# RGB_LED.net
KiCad netlist of a schematic drawn in Altium Designer
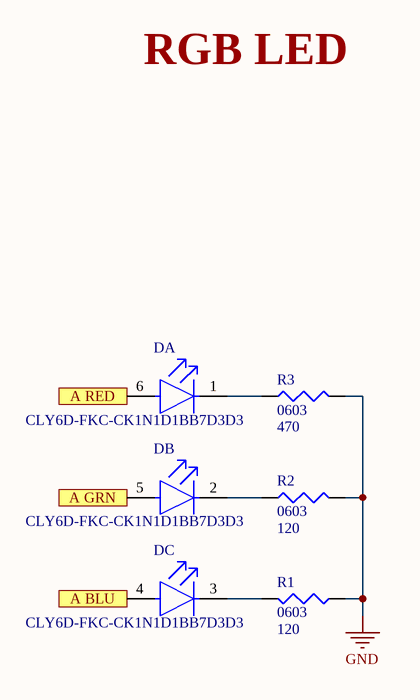
[diagram p0: RGB LED.SchDoc]

(export (version "E")
  (design (tool "Eeschema 10.0.6"))
  (components
    (comp (ref "D")
      (value "CLY6D-FKC-CK1N1D1BB7D3D3")
      (footprint "FP-CLY6D-FKC-MFG")
      (description "LED RGB DIFFUSED 6PLCC SMD")
      (libsource (lib "Altium Content Vault") (part "675964bc96c2f6a68928e7004de3fc3"))
    )
    (comp (ref "R1")
      (value "0603")
      (footprint "J1-0603")
      (description "Resistor")
      (fields (field (name "ALTIUM_VALUE") "120") (field (name "PUBLISHER") "Altium Limited"))
      (libsource (lib "Miscellaneous Devices") (part "Res3"))
    )
    (comp (ref "R2")
      (value "0603")
      (footprint "J1-0603")
      (description "Resistor")
      (fields (field (name "ALTIUM_VALUE") "120") (field (name "PUBLISHER") "Altium Limited"))
      (libsource (lib "Miscellaneous Devices") (part "Res3"))
    )
    (comp (ref "R3")
      (value "0603")
      (footprint "J1-0603")
      (description "Resistor")
      (fields (field (name "ALTIUM_VALUE") "470") (field (name "PUBLISHER") "Altium Limited"))
      (libsource (lib "Miscellaneous Devices") (part "Res3"))
    )
  )
  (nets
    (net (code "1") (name "/A BLU") (class "Default")
      (node (ref "D") (pin "4") (pinfunction "RED(A)_4") (pintype "passive"))
    )
    (net (code "2") (name "/A GRN") (class "Default")
      (node (ref "D") (pin "5") (pinfunction "GREEN(A)_5") (pintype "passive"))
    )
    (net (code "3") (name "/A RED") (class "Default")
      (node (ref "D") (pin "6") (pinfunction "BLUE(A)_6") (pintype "passive"))
    )
    (net (code "4") (name "GND") (class "Default")
      (node (ref "R1") (pin "1") (pinfunction "1_1") (pintype "passive"))
      (node (ref "R2") (pin "2") (pinfunction "2_2") (pintype "passive"))
      (node (ref "R3") (pin "2") (pinfunction "2_2") (pintype "passive"))
    )
    (net (code "5") (name "Net-(DA-BLUE(C))") (class "Default")
      (node (ref "D") (pin "1") (pinfunction "BLUE(C)_1") (pintype "passive"))
      (node (ref "R3") (pin "1") (pinfunction "1_1") (pintype "passive"))
    )
    (net (code "6") (name "Net-(DB-GREEN(C))") (class "Default")
      (node (ref "D") (pin "2") (pinfunction "GREEN(C)_2") (pintype "passive"))
      (node (ref "R2") (pin "1") (pinfunction "1_1") (pintype "passive"))
    )
    (net (code "7") (name "Net-(DC-RED(C))") (class "Default")
      (node (ref "D") (pin "3") (pinfunction "RED(C)_3") (pintype "passive"))
      (node (ref "R1") (pin "2") (pinfunction "2_2") (pintype "passive"))
    )
  )
)
